# Output.net
KiCad netlist of a schematic drawn in Altium Designer
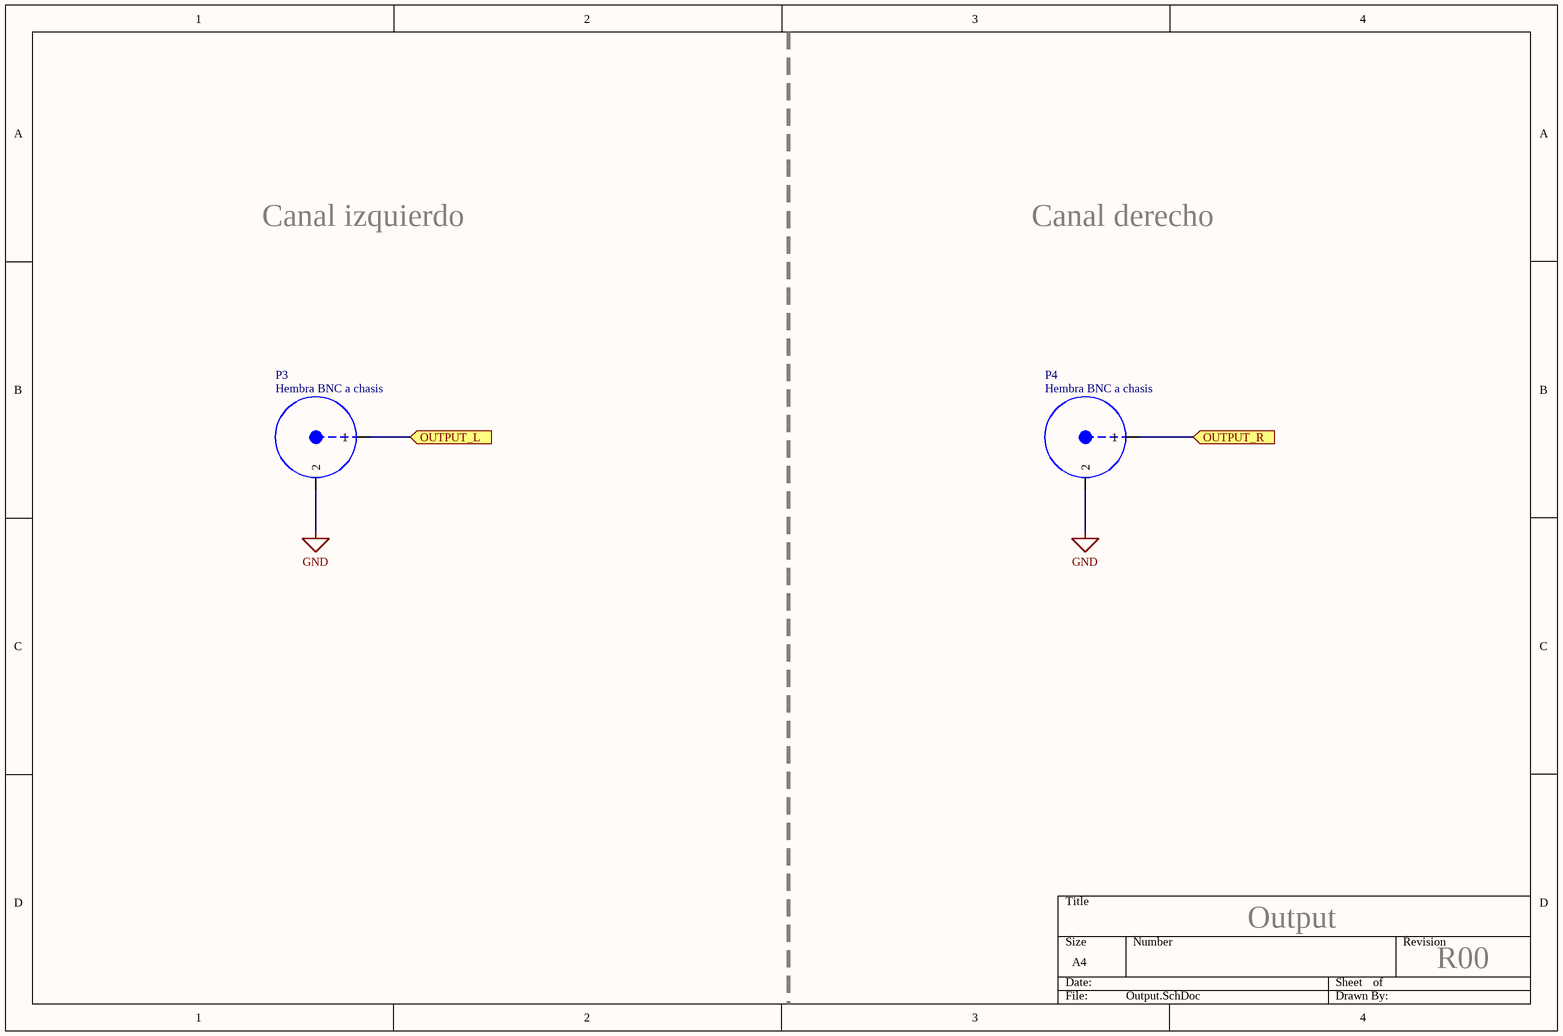
[diagram p0: Output.SchDoc]

(export (version "E")
  (design (tool "Eeschema 10.0.6"))
  (components
    (comp (ref "P3")
      (value "Hembra BNC a chasis")
      (footprint "BNC_Ext")
      (description "BNC connector")
      (libsource (lib "Radios_Comunitarias") (part "BNC"))
    )
    (comp (ref "P4")
      (value "Hembra BNC a chasis")
      (footprint "BNC_Ext")
      (description "BNC connector")
      (libsource (lib "Radios_Comunitarias") (part "BNC"))
    )
  )
  (nets
    (net (code "1") (name "/OUTPUT_L") (class "Default")
      (node (ref "P3") (pin "1") (pinfunction "1_1") (pintype "passive"))
    )
    (net (code "2") (name "/OUTPUT_R") (class "Default")
      (node (ref "P4") (pin "1") (pinfunction "1_1") (pintype "passive"))
    )
    (net (code "3") (name "GND") (class "Default")
      (node (ref "P3") (pin "2") (pinfunction "2_2") (pintype "passive"))
      (node (ref "P4") (pin "2") (pinfunction "2_2") (pintype "passive"))
    )
  )
)
